# LM_HTR_001.net
KiCad netlist of a schematic drawn in Altium Designer
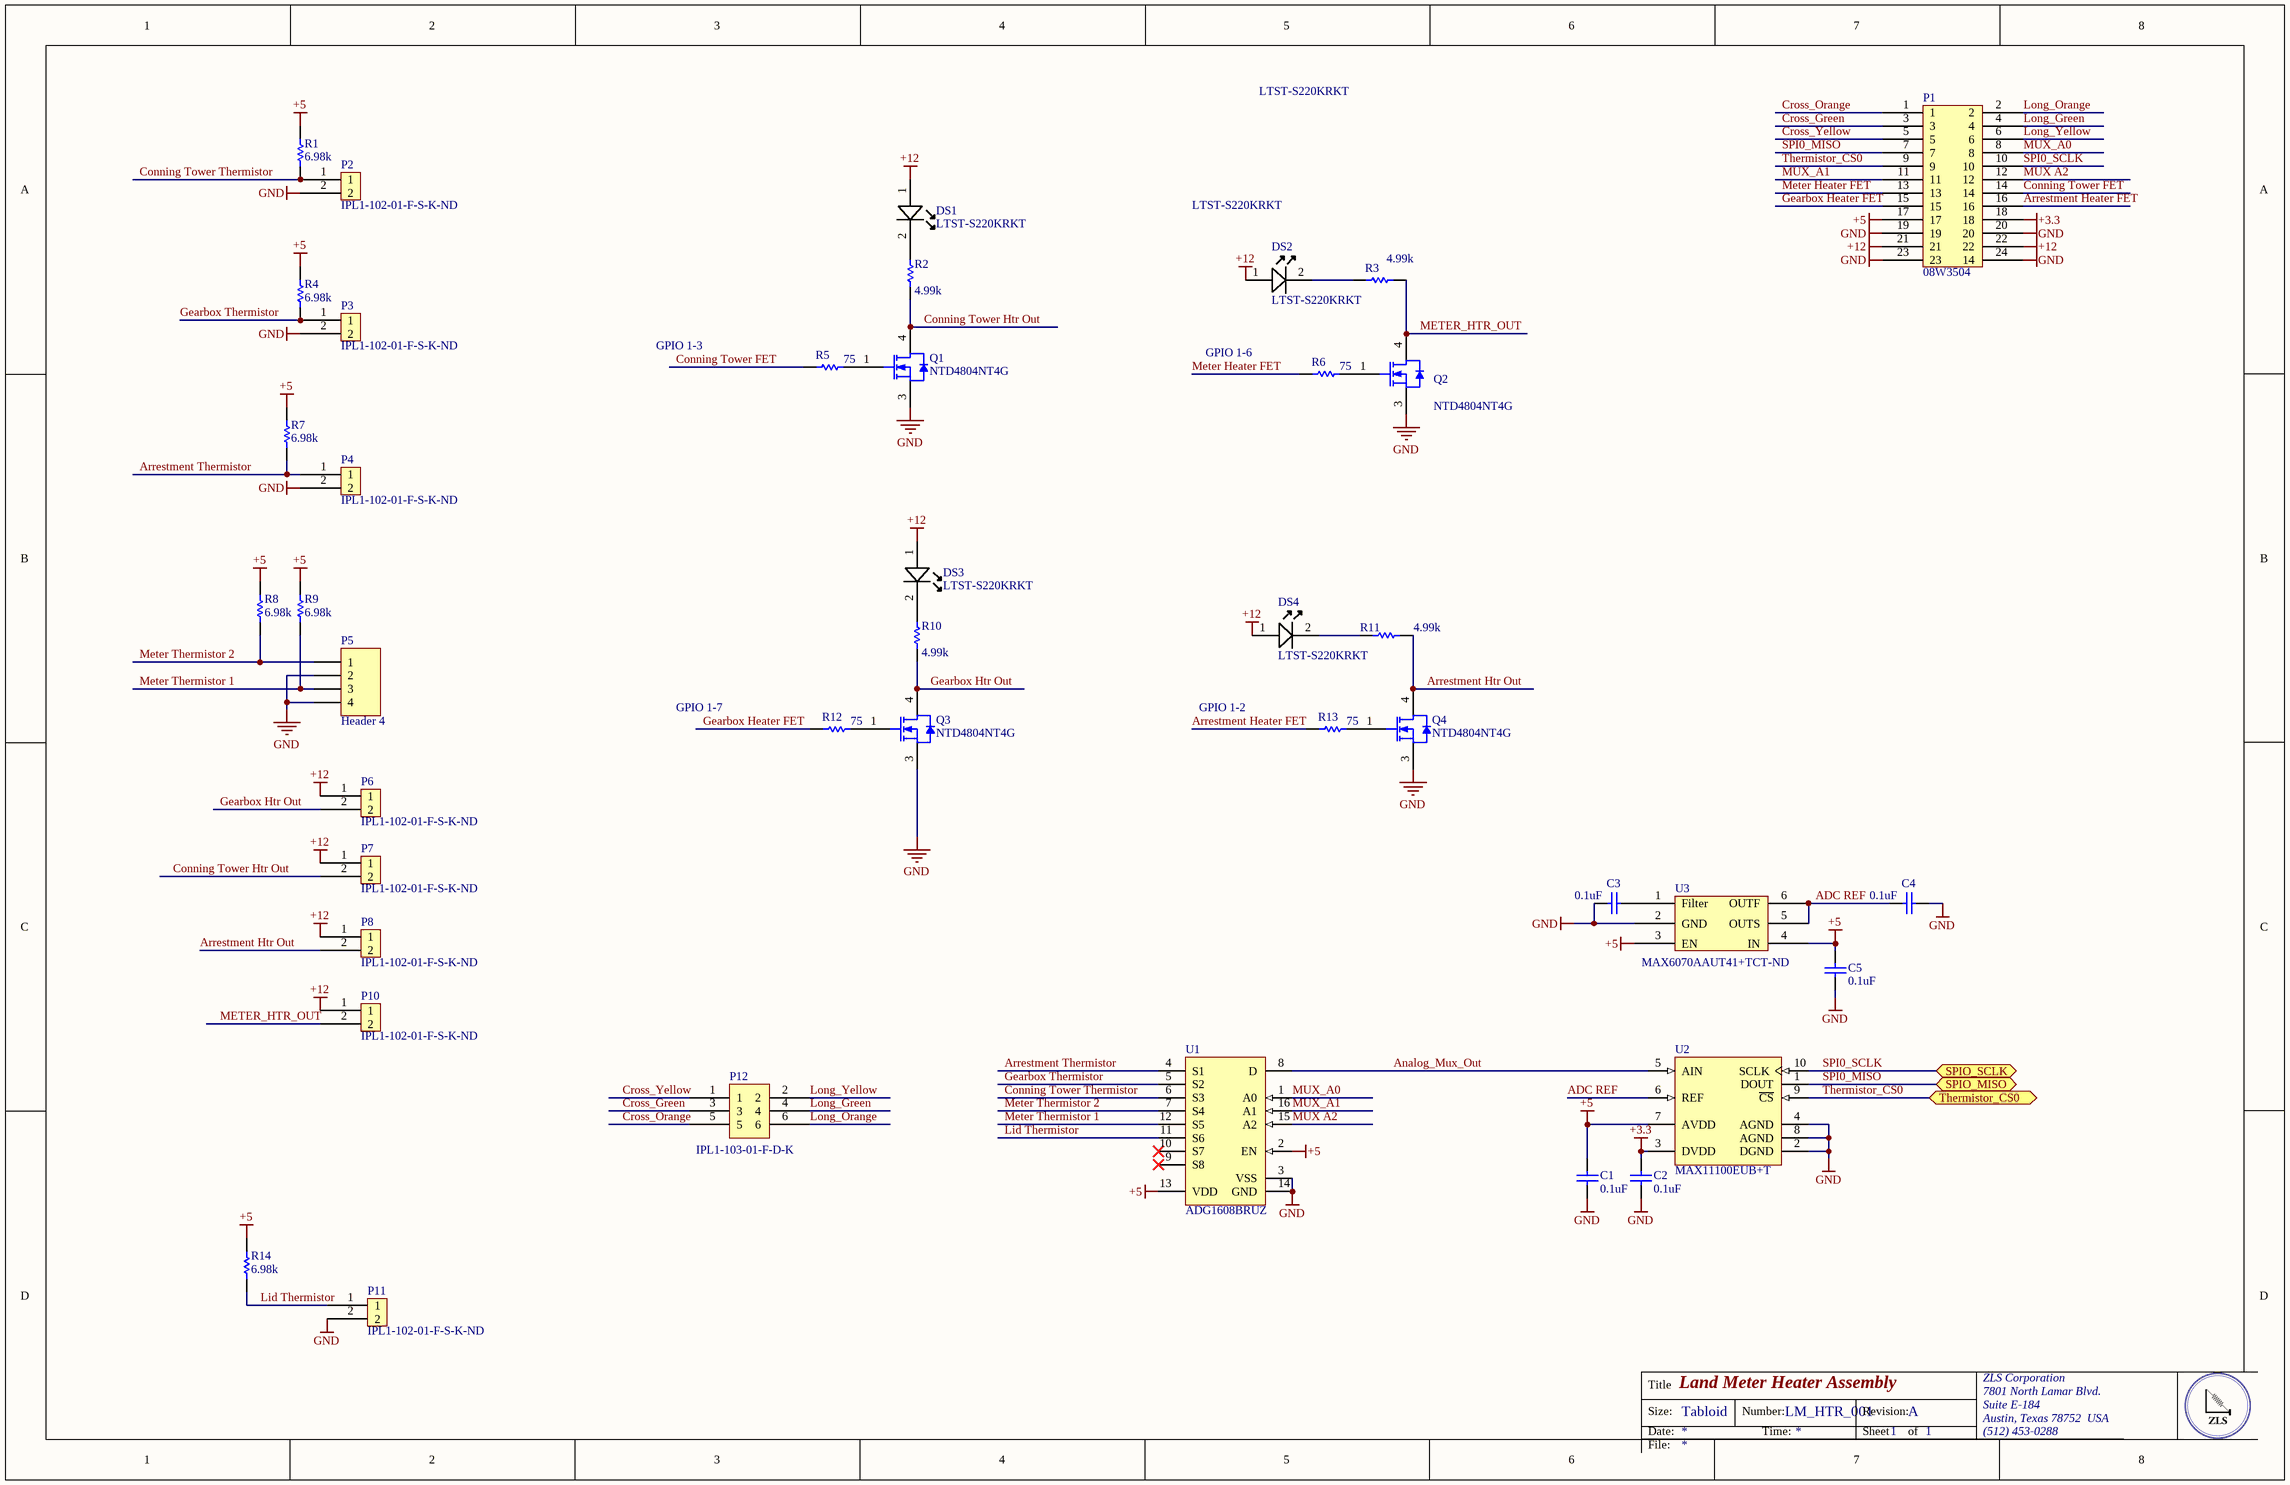
[diagram p0: LM_HTR_001.SchDoc]

(export (version "E")
  (design (tool "Eeschema 10.0.6"))
  (components
    (comp (ref "C1")
      (value "0.1uF")
      (footprint "CAPC0402(1005)60_L")
      (description "CAP CER 0.1UF 10V X7R 0402")
      (fields
        (field (name "MANUFACTURER") "Murata Electronics North America")
        (field (name "MANUFACTURER PART NUMBER") "GRM155R71A104KA01D")
      )
      (libsource (lib "Altium Content Vault") (part "CMP-1034-00252-1"))
    )
    (comp (ref "C2")
      (value "0.1uF")
      (footprint "CAPC0402(1005)60_L")
      (description "CAP CER 0.1UF 10V X7R 0402")
      (fields
        (field (name "MANUFACTURER") "Murata Electronics North America")
        (field (name "MANUFACTURER PART NUMBER") "GRM155R71A104KA01D")
      )
      (libsource (lib "Altium Content Vault") (part "CMP-1034-00252-1"))
    )
    (comp (ref "C3")
      (value "0.1uF")
      (footprint "CAPC0402(1005)60_L")
      (description "CAP CER 0.1UF 10V X7R 0402")
      (fields
        (field (name "MANUFACTURER") "Murata Electronics North America")
        (field (name "MANUFACTURER PART NUMBER") "GRM155R71A104KA01D")
      )
      (libsource (lib "Altium Content Vault") (part "CMP-1034-00252-1"))
    )
    (comp (ref "C4")
      (value "0.1uF")
      (footprint "CAPC0402(1005)60_L")
      (description "CAP CER 0.1UF 10V X7R 0402")
      (fields
        (field (name "MANUFACTURER") "Murata Electronics North America")
        (field (name "MANUFACTURER PART NUMBER") "GRM155R71A104KA01D")
      )
      (libsource (lib "Altium Content Vault") (part "CMP-1034-00252-1"))
    )
    (comp (ref "C5")
      (value "0.1uF")
      (footprint "CAPC0402(1005)60_L")
      (description "CAP CER 0.1UF 10V X7R 0402")
      (fields
        (field (name "MANUFACTURER") "Murata Electronics North America")
        (field (name "MANUFACTURER PART NUMBER") "GRM155R71A104KA01D")
      )
      (libsource (lib "Altium Content Vault") (part "CMP-1034-00252-1"))
    )
    (comp (ref "DS1")
      (value "Visible Name Value Type    False Description Lite-On LTST-S220KRKT Red LED, 631 nm 2012 (0805) Side View, Rectangle Lens SMD package STRING")
      (footprint "0805C_L")
      (fields
        (field (name "MANUFACTURER") "Vishay / Lite-On")
        (field (name "MANUFACTURER PART NUMBER") "LTST-S220KRKT")
      )
      (libsource (lib "*") (part "LED A/K"))
    )
    (comp (ref "DS2")
      (value "Visible Name Value Type    False Description Lite-On LTST-S220KRKT Red LED, 631 nm 2012 (0805) Side View, Rectangle Lens SMD package STRING")
      (footprint "0805C_L")
      (fields
        (field (name "MANUFACTURER") "Vishay / Lite-On")
        (field (name "MANUFACTURER PART NUMBER") "LTST-S220KRKT")
      )
      (libsource (lib "*") (part "LED A/K"))
    )
    (comp (ref "DS3")
      (value "Visible Name Value Type    False Description Lite-On LTST-S220KRKT Red LED, 631 nm 2012 (0805) Side View, Rectangle Lens SMD package STRING")
      (footprint "0805C_L")
      (fields
        (field (name "MANUFACTURER") "Vishay / Lite-On")
        (field (name "MANUFACTURER PART NUMBER") "LTST-S220KRKT")
      )
      (libsource (lib "*") (part "LED A/K"))
    )
    (comp (ref "DS4")
      (value "Visible Name Value Type    False Description Lite-On LTST-S220KRKT Red LED, 631 nm 2012 (0805) Side View, Rectangle Lens SMD package STRING")
      (footprint "0805C_L")
      (fields
        (field (name "MANUFACTURER") "Vishay / Lite-On")
        (field (name "MANUFACTURER PART NUMBER") "LTST-S220KRKT")
      )
      (libsource (lib "*") (part "LED A/K"))
    )
    (comp (ref "P1")
      (value "IPL1-112-01-F-S-K")
      (footprint "IPL1-112-01-F-S-K")
      (description "IPL1-112-01-F-D-K")
      (fields (field (name "SUPPLIER PART NUMBER 1") "08W3504"))
      (libsource (lib "ZLS_Schematic_lib") (part "IPL1-112-01-F-S-K"))
    )
    (comp (ref "P2")
      (value "IPL1-102-01-F-S-K")
      (footprint "IPL1-102-01-F-S-K")
      (description ".100 TERMINAL ASSEMBLY")
      (fields
        (field (name "SUPPLIER PART NUMBER 1") "IPL1-102-01-F-S-K-ND")
        (field (name "MANUFACTURER") "Samtec Inc.")
      )
      (libsource (lib "ZLS_Schematic_lib") (part "IPL1-102-01-F-S-K"))
    )
    (comp (ref "P3")
      (value "IPL1-102-01-F-S-K")
      (footprint "IPL1-102-01-F-S-K")
      (description ".100 TERMINAL ASSEMBLY")
      (fields
        (field (name "SUPPLIER PART NUMBER 1") "IPL1-102-01-F-S-K-ND")
        (field (name "MANUFACTURER") "Samtec Inc.")
      )
      (libsource (lib "ZLS_Schematic_lib") (part "IPL1-102-01-F-S-K"))
    )
    (comp (ref "P4")
      (value "IPL1-102-01-F-S-K")
      (footprint "IPL1-102-01-F-S-K")
      (description ".100 TERMINAL ASSEMBLY")
      (fields
        (field (name "SUPPLIER PART NUMBER 1") "IPL1-102-01-F-S-K-ND")
        (field (name "MANUFACTURER") "Samtec Inc.")
      )
      (libsource (lib "ZLS_Schematic_lib") (part "IPL1-102-01-F-S-K"))
    )
    (comp (ref "P5")
      (value "Header 4")
      (footprint "IPL1-104-01-L-S-K")
      (description "Header, 4-Pin")
      (fields (field (name "PUBLISHER") "Altium Limited"))
      (libsource (lib "Miscellaneous Connectors") (part "Header 4"))
    )
    (comp (ref "P6")
      (value "IPL1-102-01-F-S-K")
      (footprint "IPL1-102-01-F-S-K")
      (description ".100 TERMINAL ASSEMBLY")
      (fields
        (field (name "SUPPLIER PART NUMBER 1") "IPL1-102-01-F-S-K-ND")
        (field (name "MANUFACTURER") "Samtec Inc.")
      )
      (libsource (lib "ZLS_Schematic_lib") (part "IPL1-102-01-F-S-K"))
    )
    (comp (ref "P7")
      (value "IPL1-102-01-F-S-K")
      (footprint "IPL1-102-01-F-S-K")
      (description ".100 TERMINAL ASSEMBLY")
      (fields
        (field (name "SUPPLIER PART NUMBER 1") "IPL1-102-01-F-S-K-ND")
        (field (name "MANUFACTURER") "Samtec Inc.")
      )
      (libsource (lib "ZLS_Schematic_lib") (part "IPL1-102-01-F-S-K"))
    )
    (comp (ref "P8")
      (value "IPL1-102-01-F-S-K")
      (footprint "IPL1-102-01-F-S-K")
      (description ".100 TERMINAL ASSEMBLY")
      (fields
        (field (name "SUPPLIER PART NUMBER 1") "IPL1-102-01-F-S-K-ND")
        (field (name "MANUFACTURER") "Samtec Inc.")
      )
      (libsource (lib "ZLS_Schematic_lib") (part "IPL1-102-01-F-S-K"))
    )
    (comp (ref "P10")
      (value "IPL1-102-01-F-S-K")
      (footprint "IPL1-102-01-F-S-K")
      (description ".100 TERMINAL ASSEMBLY")
      (fields
        (field (name "SUPPLIER PART NUMBER 1") "IPL1-102-01-F-S-K-ND")
        (field (name "MANUFACTURER") "Samtec Inc.")
      )
      (libsource (lib "ZLS_Schematic_lib") (part "IPL1-102-01-F-S-K"))
    )
    (comp (ref "P11")
      (value "IPL1-102-01-F-S-K")
      (footprint "IPL1-102-01-F-S-K")
      (description ".100 TERMINAL ASSEMBLY")
      (fields
        (field (name "SUPPLIER PART NUMBER 1") "IPL1-102-01-F-S-K-ND")
        (field (name "MANUFACTURER") "Samtec Inc.")
      )
      (libsource (lib "ZLS_Schematic_lib") (part "IPL1-102-01-F-S-K"))
    )
    (comp (ref "P12")
      (value "IPL1-103-01-F-D")
      (footprint "IPL1-103-01-F-D")
      (fields
        (field (name "MANUFACTURER") "SAMTEC")
        (field (name "MANUFACTURER PART NUMBER") "IPL1-103-01-F-D-K")
        (field (name "COMPONENTLINK1URL") "https://webassistants.partcommunity.com/23d-libs/samtec/search/resolve.html?EMAIL=mysamtec@samtec.com&PN=HTSW-114-05-F-D")
        (field (name "COMPONENTLINK1DESCRIPTION") "https://webassistants.partcommunity.com/23d-libs/samtec/search/resolve.html?EMAIL=mysamtec@samtec.com&PN=HTSW-114-05-F-D")
      )
      (libsource (lib "ZLS_Schematic_lib") (part "IPL1-103-01-F-D"))
    )
    (comp (ref "Q1")
      (value "NTD4804NT4G")
      (footprint "ONSC-DPAK-3-369AA-01_V")
      (description "Power MOSFET, 30 V, 117 A, Single N-Channel, 3-Pin DPAK, Pb-Free, Tape and Reel")
      (fields (field (name "MANUFACTURER") "On Semiconductor"))
      (libsource (lib "Altium Content Vault") (part "CMP-1058-00341-1"))
    )
    (comp (ref "Q2")
      (value "NTD4804NT4G")
      (footprint "ONSC-DPAK-3-369AA-01_V")
      (description "Power MOSFET, 30 V, 117 A, Single N-Channel, 3-Pin DPAK, Pb-Free, Tape and Reel")
      (fields (field (name "MANUFACTURER") "On Semiconductor"))
      (libsource (lib "Altium Content Vault") (part "CMP-1058-00341-1"))
    )
    (comp (ref "Q3")
      (value "NTD4804NT4G")
      (footprint "ONSC-DPAK-3-369AA-01_V")
      (description "Power MOSFET, 30 V, 117 A, Single N-Channel, 3-Pin DPAK, Pb-Free, Tape and Reel")
      (fields (field (name "MANUFACTURER") "On Semiconductor"))
      (libsource (lib "Altium Content Vault") (part "CMP-1058-00341-1"))
    )
    (comp (ref "Q4")
      (value "NTD4804NT4G")
      (footprint "ONSC-DPAK-3-369AA-01_V")
      (description "Power MOSFET, 30 V, 117 A, Single N-Channel, 3-Pin DPAK, Pb-Free, Tape and Reel")
      (fields (field (name "MANUFACTURER") "On Semiconductor"))
      (libsource (lib "Altium Content Vault") (part "CMP-1058-00341-1"))
    )
    (comp (ref "R1")
      (value "6K98 1% 0805(2012)")
      (footprint "RESC0805(2012)_N")
      (description "6K98 0.125W 1% 0805 (2012 Metric)  SMD")
      (fields
        (field (name "MANUFACTURER") "Vishay Dale")
        (field (name "MANUFACTURER PART NUMBER") "CRCW08056K98FKEA")
        (field (name "RESISTANCE (OHMS)") "6.98k")
      )
      (libsource (lib "Altium Content Vault") (part "CMP-1013-00606-1"))
    )
    (comp (ref "R2")
      (value "~")
      (footprint "RESC0805(2012)_L")
      (fields
        (field (name "MANUFACTURER") "Vishay Dale")
        (field (name "MANUFACTURER PART NUMBER") "CRCW08054K99FKEA")
        (field (name "RESISTANCE (OHMS)") "4.99k")
        (field (name "TOLERANCE") "±1%")
      )
      (libsource (lib "Altium Content Vault") (part "CMP-1013-00393-1"))
    )
    (comp (ref "R3")
      (value "~")
      (footprint "RESC0805(2012)_L")
      (fields
        (field (name "MANUFACTURER") "Vishay Dale")
        (field (name "MANUFACTURER PART NUMBER") "CRCW08054K99FKEA")
        (field (name "RESISTANCE (OHMS)") "4.99k")
        (field (name "TOLERANCE") "±1%")
      )
      (libsource (lib "Altium Content Vault") (part "CMP-1013-00393-1"))
    )
    (comp (ref "R4")
      (value "6K98 1% 0805(2012)")
      (footprint "RESC0805(2012)_N")
      (description "6K98 0.125W 1% 0805 (2012 Metric)  SMD")
      (fields
        (field (name "MANUFACTURER") "Vishay Dale")
        (field (name "MANUFACTURER PART NUMBER") "CRCW08056K98FKEA")
        (field (name "RESISTANCE (OHMS)") "6.98k")
      )
      (libsource (lib "Altium Content Vault") (part "CMP-1013-00606-1"))
    )
    (comp (ref "R5")
      (value "~")
      (footprint "RESC0805(2012)_L")
      (fields
        (field (name "MANUFACTURER") "Vishay Dale")
        (field (name "MANUFACTURER PART NUMBER") "CRCW080575R0FKEA")
        (field (name "RESISTANCE (OHMS)") "75")
        (field (name "TOLERANCE") "±1%")
      )
      (libsource (lib "Altium Content Vault") (part "CMP-1013-00393-1"))
    )
    (comp (ref "R6")
      (value "~")
      (footprint "RESC0805(2012)_L")
      (fields
        (field (name "MANUFACTURER") "Vishay Dale")
        (field (name "MANUFACTURER PART NUMBER") "CRCW080575R0FKEA")
        (field (name "RESISTANCE (OHMS)") "75")
        (field (name "TOLERANCE") "±1%")
      )
      (libsource (lib "Altium Content Vault") (part "CMP-1013-00393-1"))
    )
    (comp (ref "R7")
      (value "6K98 1% 0805(2012)")
      (footprint "RESC0805(2012)_N")
      (description "6K98 0.125W 1% 0805 (2012 Metric)  SMD")
      (fields
        (field (name "MANUFACTURER") "Vishay Dale")
        (field (name "MANUFACTURER PART NUMBER") "CRCW08056K98FKEA")
        (field (name "RESISTANCE (OHMS)") "6.98k")
      )
      (libsource (lib "Altium Content Vault") (part "CMP-1013-00606-1"))
    )
    (comp (ref "R8")
      (value "6K98 1% 0805(2012)")
      (footprint "RESC0805(2012)_N")
      (description "6K98 0.125W 1% 0805 (2012 Metric)  SMD")
      (fields
        (field (name "MANUFACTURER") "Vishay Dale")
        (field (name "MANUFACTURER PART NUMBER") "CRCW08056K98FKEA")
        (field (name "RESISTANCE (OHMS)") "6.98k")
      )
      (libsource (lib "Altium Content Vault") (part "CMP-1013-00606-1"))
    )
    (comp (ref "R9")
      (value "6K98 1% 0805(2012)")
      (footprint "RESC0805(2012)_N")
      (description "6K98 0.125W 1% 0805 (2012 Metric)  SMD")
      (fields
        (field (name "MANUFACTURER") "Vishay Dale")
        (field (name "MANUFACTURER PART NUMBER") "CRCW08056K98FKEA")
        (field (name "RESISTANCE (OHMS)") "6.98k")
      )
      (libsource (lib "Altium Content Vault") (part "CMP-1013-00606-1"))
    )
    (comp (ref "R10")
      (value "~")
      (footprint "RESC0805(2012)_L")
      (fields
        (field (name "MANUFACTURER") "Vishay Dale")
        (field (name "MANUFACTURER PART NUMBER") "CRCW08054K99FKEA")
        (field (name "RESISTANCE (OHMS)") "4.99k")
        (field (name "TOLERANCE") "±1%")
      )
      (libsource (lib "Altium Content Vault") (part "CMP-1013-00393-1"))
    )
    (comp (ref "R11")
      (value "~")
      (footprint "RESC0805(2012)_L")
      (fields
        (field (name "MANUFACTURER") "Vishay Dale")
        (field (name "MANUFACTURER PART NUMBER") "CRCW08054K99FKEA")
        (field (name "RESISTANCE (OHMS)") "4.99k")
        (field (name "TOLERANCE") "±1%")
      )
      (libsource (lib "Altium Content Vault") (part "CMP-1013-00393-1"))
    )
    (comp (ref "R12")
      (value "~")
      (footprint "RESC0805(2012)_L")
      (fields
        (field (name "MANUFACTURER") "Vishay Dale")
        (field (name "MANUFACTURER PART NUMBER") "CRCW080575R0FKEA")
        (field (name "RESISTANCE (OHMS)") "75")
        (field (name "TOLERANCE") "±1%")
      )
      (libsource (lib "Altium Content Vault") (part "CMP-1013-00393-1"))
    )
    (comp (ref "R13")
      (value "~")
      (footprint "RESC0805(2012)_L")
      (fields
        (field (name "MANUFACTURER") "Vishay Dale")
        (field (name "MANUFACTURER PART NUMBER") "CRCW080575R0FKEA")
        (field (name "RESISTANCE (OHMS)") "75")
        (field (name "TOLERANCE") "±1%")
      )
      (libsource (lib "Altium Content Vault") (part "CMP-1013-00393-1"))
    )
    (comp (ref "R14")
      (value "6K98 1% 0805(2012)")
      (footprint "RESC0805(2012)_N")
      (description "6K98 0.125W 1% 0805 (2012 Metric)  SMD")
      (fields
        (field (name "MANUFACTURER") "Vishay Dale")
        (field (name "MANUFACTURER PART NUMBER") "CRCW08056K98FKEA")
        (field (name "RESISTANCE (OHMS)") "6.98k")
      )
      (libsource (lib "Altium Content Vault") (part "CMP-1013-00606-1"))
    )
    (comp (ref "U1")
      (value "ADG1608BRUZ")
      (footprint "ADI-RU-16_M")
      (description "4.5 Ohm Ron, 8-Channel +/-5 V,+12 V, +5 V and +3.3 V Multiplexer, 16-pin SOP (RU-16), Tube")
      (fields (field (name "MANUFACTURER") "Analog Devices"))
      (libsource (lib "Altium Content Vault") (part "ADI-ADG1608-RU-16"))
    )
    (comp (ref "U2")
      (value "MAX11100EUB+T")
      (footprint "U10+2_L")
      (description "16-Bit, +5V, 200ksps ADC with 10uA Shutdown, 10-Pin uMAX, -40°C to +85°C, Pb-Free, Tape and Reel")
      (libsource (lib "Altium Content Vault") (part "CON-ADC-MAX11100-IL10"))
    )
    (comp (ref "U3")
      (value "MAX6070AAUT41+T")
      (footprint "SOT95P280X445-6N")
      (description "IC VREF SERIES 4.096V SOT23")
      (fields
        (field (name "SUPPLIER PART NUMBER 1") "MAX6070AAUT41+TCT-ND")
        (field (name "MANUFACTURER") "Maxim Integrated")
        (field (name "TOLERANCE") "±0.04%")
      )
      (libsource (lib "ZLS_Schematic_lib") (part "MAX6070AAUT41+T"))
    )
  )
  (nets
    (net (code "1") (name "+3.3") (class "Default")
      (node (ref "C2") (pin "1") (pinfunction "1_1") (pintype "passive"))
      (node (ref "P1") (pin "18") (pinfunction "18_18") (pintype "passive"))
      (node (ref "U2") (pin "3") (pinfunction "DVDD_3") (pintype "power_in"))
    )
    (net (code "2") (name "+5") (class "Default")
      (node (ref "C1") (pin "1") (pinfunction "1_1") (pintype "passive"))
      (node (ref "C5") (pin "1") (pinfunction "1_1") (pintype "passive"))
      (node (ref "P1") (pin "17") (pinfunction "17_17") (pintype "passive"))
      (node (ref "R1") (pin "2") (pinfunction "2_2") (pintype "passive"))
      (node (ref "R14") (pin "1") (pinfunction "1_1") (pintype "passive"))
      (node (ref "R4") (pin "2") (pinfunction "2_2") (pintype "passive"))
      (node (ref "R7") (pin "1") (pinfunction "1_1") (pintype "passive"))
      (node (ref "R8") (pin "1") (pinfunction "1_1") (pintype "passive"))
      (node (ref "R9") (pin "2") (pinfunction "2_2") (pintype "passive"))
      (node (ref "U1") (pin "13") (pinfunction "VDD_13") (pintype "power_in"))
      (node (ref "U1") (pin "2") (pinfunction "EN_2") (pintype "input"))
      (node (ref "U2") (pin "7") (pinfunction "AVDD_7") (pintype "power_in"))
      (node (ref "U3") (pin "3") (pinfunction "EN_3") (pintype "passive"))
      (node (ref "U3") (pin "4") (pinfunction "IN_4") (pintype "passive"))
    )
    (net (code "3") (name "+12") (class "Default")
      (node (ref "DS1") (pin "1") (pinfunction "A_1") (pintype "passive"))
      (node (ref "DS2") (pin "1") (pinfunction "A_1") (pintype "passive"))
      (node (ref "DS3") (pin "1") (pinfunction "A_1") (pintype "passive"))
      (node (ref "DS4") (pin "1") (pinfunction "A_1") (pintype "passive"))
      (node (ref "P1") (pin "21") (pinfunction "21_21") (pintype "passive"))
      (node (ref "P1") (pin "22") (pinfunction "22_22") (pintype "passive"))
      (node (ref "P10") (pin "1") (pinfunction "1_1") (pintype "passive"))
      (node (ref "P6") (pin "1") (pinfunction "1_1") (pintype "passive"))
      (node (ref "P7") (pin "1") (pinfunction "1_1") (pintype "passive"))
      (node (ref "P8") (pin "1") (pinfunction "1_1") (pintype "passive"))
    )
    (net (code "4") (name "/ADC REF") (class "Default")
      (node (ref "C4") (pin "2") (pinfunction "2_2") (pintype "passive"))
      (node (ref "U2") (pin "6") (pinfunction "REF_6") (pintype "input"))
      (node (ref "U3") (pin "5") (pinfunction "OUTS_5") (pintype "passive"))
      (node (ref "U3") (pin "6") (pinfunction "OUTF_6") (pintype "passive"))
    )
    (net (code "5") (name "/Analog_Mux_Out") (class "Default")
      (node (ref "U1") (pin "8") (pinfunction "D_8") (pintype "passive"))
      (node (ref "U2") (pin "5") (pinfunction "AIN_5") (pintype "input"))
    )
    (net (code "6") (name "/Arrestment Heater FET") (class "Default")
      (node (ref "P1") (pin "16") (pinfunction "16_16") (pintype "passive"))
      (node (ref "R13") (pin "1") (pinfunction "1_1") (pintype "passive"))
    )
    (net (code "7") (name "/Arrestment Htr Out") (class "Default")
      (node (ref "P8") (pin "2") (pinfunction "2_2") (pintype "passive"))
      (node (ref "Q4") (pin "4") (pinfunction "D_4") (pintype "passive"))
      (node (ref "R11") (pin "2") (pinfunction "2_2") (pintype "passive"))
    )
    (net (code "8") (name "/Arrestment Thermistor") (class "Default")
      (node (ref "P4") (pin "1") (pinfunction "1_1") (pintype "passive"))
      (node (ref "R7") (pin "2") (pinfunction "2_2") (pintype "passive"))
      (node (ref "U1") (pin "4") (pinfunction "S1_4") (pintype "passive"))
    )
    (net (code "9") (name "/Conning Tower FET") (class "Default")
      (node (ref "P1") (pin "14") (pinfunction "14_14") (pintype "passive"))
      (node (ref "R5") (pin "1") (pinfunction "1_1") (pintype "passive"))
    )
    (net (code "10") (name "/Conning Tower Htr Out") (class "Default")
      (node (ref "P7") (pin "2") (pinfunction "2_2") (pintype "passive"))
      (node (ref "Q1") (pin "4") (pinfunction "D_4") (pintype "passive"))
      (node (ref "R2") (pin "1") (pinfunction "1_1") (pintype "passive"))
    )
    (net (code "11") (name "/Conning Tower Thermistor") (class "Default")
      (node (ref "P2") (pin "1") (pinfunction "1_1") (pintype "passive"))
      (node (ref "R1") (pin "1") (pinfunction "1_1") (pintype "passive"))
      (node (ref "U1") (pin "6") (pinfunction "S3_6") (pintype "passive"))
    )
    (net (code "12") (name "/Cross_Green") (class "Default")
      (node (ref "P1") (pin "3") (pinfunction "3_3") (pintype "passive"))
      (node (ref "P12") (pin "3") (pinfunction "3_3") (pintype "passive"))
    )
    (net (code "13") (name "/Cross_Orange") (class "Default")
      (node (ref "P1") (pin "1") (pinfunction "1_1") (pintype "passive"))
      (node (ref "P12") (pin "5") (pinfunction "5_5") (pintype "passive"))
    )
    (net (code "14") (name "/Cross_Yellow") (class "Default")
      (node (ref "P1") (pin "5") (pinfunction "5_5") (pintype "passive"))
      (node (ref "P12") (pin "1") (pinfunction "1_1") (pintype "passive"))
    )
    (net (code "15") (name "/Gearbox Heater FET") (class "Default")
      (node (ref "P1") (pin "15") (pinfunction "15_15") (pintype "passive"))
      (node (ref "R12") (pin "1") (pinfunction "1_1") (pintype "passive"))
    )
    (net (code "16") (name "/Gearbox Htr Out") (class "Default")
      (node (ref "P6") (pin "2") (pinfunction "2_2") (pintype "passive"))
      (node (ref "Q3") (pin "4") (pinfunction "D_4") (pintype "passive"))
      (node (ref "R10") (pin "1") (pinfunction "1_1") (pintype "passive"))
    )
    (net (code "17") (name "/Gearbox Thermistor") (class "Default")
      (node (ref "P3") (pin "1") (pinfunction "1_1") (pintype "passive"))
      (node (ref "R4") (pin "1") (pinfunction "1_1") (pintype "passive"))
      (node (ref "U1") (pin "5") (pinfunction "S2_5") (pintype "passive"))
    )
    (net (code "18") (name "/Lid Thermistor") (class "Default")
      (node (ref "P11") (pin "1") (pinfunction "1_1") (pintype "passive"))
      (node (ref "R14") (pin "2") (pinfunction "2_2") (pintype "passive"))
      (node (ref "U1") (pin "11") (pinfunction "S6_11") (pintype "passive"))
    )
    (net (code "19") (name "/Long_Green") (class "Default")
      (node (ref "P1") (pin "4") (pinfunction "4_4") (pintype "passive"))
      (node (ref "P12") (pin "4") (pinfunction "4_4") (pintype "passive"))
    )
    (net (code "20") (name "/Long_Orange") (class "Default")
      (node (ref "P1") (pin "2") (pinfunction "2_2") (pintype "passive"))
      (node (ref "P12") (pin "6") (pinfunction "6_6") (pintype "passive"))
    )
    (net (code "21") (name "/Long_Yellow") (class "Default")
      (node (ref "P1") (pin "6") (pinfunction "6_6") (pintype "passive"))
      (node (ref "P12") (pin "2") (pinfunction "2_2") (pintype "passive"))
    )
    (net (code "22") (name "/METER_HTR_OUT") (class "Default")
      (node (ref "P10") (pin "2") (pinfunction "2_2") (pintype "passive"))
      (node (ref "Q2") (pin "4") (pinfunction "D_4") (pintype "passive"))
      (node (ref "R3") (pin "2") (pinfunction "2_2") (pintype "passive"))
    )
    (net (code "23") (name "/MUX A2") (class "Default")
      (node (ref "P1") (pin "12") (pinfunction "12_12") (pintype "passive"))
      (node (ref "U1") (pin "15") (pinfunction "A2_15") (pintype "input"))
    )
    (net (code "24") (name "/MUX_A0") (class "Default")
      (node (ref "P1") (pin "8") (pinfunction "8_8") (pintype "passive"))
      (node (ref "U1") (pin "1") (pinfunction "A0_1") (pintype "input"))
    )
    (net (code "25") (name "/MUX_A1") (class "Default")
      (node (ref "P1") (pin "11") (pinfunction "11_11") (pintype "passive"))
      (node (ref "U1") (pin "16") (pinfunction "A1_16") (pintype "input"))
    )
    (net (code "26") (name "/Meter Heater FET") (class "Default")
      (node (ref "P1") (pin "13") (pinfunction "13_13") (pintype "passive"))
      (node (ref "R6") (pin "1") (pinfunction "1_1") (pintype "passive"))
    )
    (net (code "27") (name "/Meter Thermistor 1") (class "Default")
      (node (ref "P5") (pin "3") (pinfunction "3_3") (pintype "passive"))
      (node (ref "R9") (pin "1") (pinfunction "1_1") (pintype "passive"))
      (node (ref "U1") (pin "12") (pinfunction "S5_12") (pintype "passive"))
    )
    (net (code "28") (name "/Meter Thermistor 2") (class "Default")
      (node (ref "P5") (pin "1") (pinfunction "1_1") (pintype "passive"))
      (node (ref "R8") (pin "2") (pinfunction "2_2") (pintype "passive"))
      (node (ref "U1") (pin "7") (pinfunction "S4_7") (pintype "passive"))
    )
    (net (code "29") (name "/SPI0_MISO") (class "Default")
      (node (ref "P1") (pin "7") (pinfunction "7_7") (pintype "passive"))
      (node (ref "U2") (pin "1") (pinfunction "DOUT_1") (pintype "tri_state"))
    )
    (net (code "30") (name "/SPI0_SCLK") (class "Default")
      (node (ref "P1") (pin "10") (pinfunction "10_10") (pintype "passive"))
      (node (ref "U2") (pin "10") (pinfunction "SCLK_10") (pintype "input"))
    )
    (net (code "31") (name "/Thermistor_CS0") (class "Default")
      (node (ref "P1") (pin "9") (pinfunction "9_9") (pintype "passive"))
      (node (ref "U2") (pin "9") (pinfunction "~{CS}_9") (pintype "input"))
    )
    (net (code "32") (name "GND") (class "Default")
      (node (ref "C1") (pin "2") (pinfunction "2_2") (pintype "passive"))
      (node (ref "C2") (pin "2") (pinfunction "2_2") (pintype "passive"))
      (node (ref "C3") (pin "2") (pinfunction "2_2") (pintype "passive"))
      (node (ref "C4") (pin "1") (pinfunction "1_1") (pintype "passive"))
      (node (ref "C5") (pin "2") (pinfunction "2_2") (pintype "passive"))
      (node (ref "P1") (pin "19") (pinfunction "19_19") (pintype "passive"))
      (node (ref "P1") (pin "20") (pinfunction "20_20") (pintype "passive"))
      (node (ref "P1") (pin "23") (pinfunction "23_23") (pintype "passive"))
      (node (ref "P1") (pin "24") (pinfunction "14_24") (pintype "passive"))
      (node (ref "P11") (pin "2") (pinfunction "2_2") (pintype "passive"))
      (node (ref "P2") (pin "2") (pinfunction "2_2") (pintype "passive"))
      (node (ref "P3") (pin "2") (pinfunction "2_2") (pintype "passive"))
      (node (ref "P4") (pin "2") (pinfunction "2_2") (pintype "passive"))
      (node (ref "P5") (pin "2") (pinfunction "2_2") (pintype "passive"))
      (node (ref "P5") (pin "4") (pinfunction "4_4") (pintype "passive"))
      (node (ref "Q1") (pin "3") (pinfunction "S_3") (pintype "passive"))
      (node (ref "Q2") (pin "3") (pinfunction "S_3") (pintype "passive"))
      (node (ref "Q3") (pin "3") (pinfunction "S_3") (pintype "passive"))
      (node (ref "Q4") (pin "3") (pinfunction "S_3") (pintype "passive"))
      (node (ref "U1") (pin "14") (pinfunction "GND_14") (pintype "power_in"))
      (node (ref "U1") (pin "3") (pinfunction "VSS_3") (pintype "power_in"))
      (node (ref "U2") (pin "2") (pinfunction "DGND_2") (pintype "power_in"))
      (node (ref "U2") (pin "4") (pinfunction "AGND_4") (pintype "power_in"))
      (node (ref "U2") (pin "8") (pinfunction "AGND_8") (pintype "power_in"))
      (node (ref "U3") (pin "2") (pinfunction "GND_2") (pintype "passive"))
    )
    (net (code "33") (name "Net-(DS1-K)") (class "Default")
      (node (ref "DS1") (pin "2") (pinfunction "K_2") (pintype "passive"))
      (node (ref "R2") (pin "2") (pinfunction "2_2") (pintype "passive"))
    )
    (net (code "34") (name "Net-(DS2-K)") (class "Default")
      (node (ref "DS2") (pin "2") (pinfunction "K_2") (pintype "passive"))
      (node (ref "R3") (pin "1") (pinfunction "1_1") (pintype "passive"))
    )
    (net (code "35") (name "Net-(DS3-K)") (class "Default")
      (node (ref "DS3") (pin "2") (pinfunction "K_2") (pintype "passive"))
      (node (ref "R10") (pin "2") (pinfunction "2_2") (pintype "passive"))
    )
    (net (code "36") (name "Net-(DS4-K)") (class "Default")
      (node (ref "DS4") (pin "2") (pinfunction "K_2") (pintype "passive"))
      (node (ref "R11") (pin "1") (pinfunction "1_1") (pintype "passive"))
    )
    (net (code "37") (name "Net-(Q1-G)") (class "Default")
      (node (ref "Q1") (pin "1") (pinfunction "G_1") (pintype "passive"))
      (node (ref "R5") (pin "2") (pinfunction "2_2") (pintype "passive"))
    )
    (net (code "38") (name "Net-(Q2-G)") (class "Default")
      (node (ref "Q2") (pin "1") (pinfunction "G_1") (pintype "passive"))
      (node (ref "R6") (pin "2") (pinfunction "2_2") (pintype "passive"))
    )
    (net (code "39") (name "Net-(Q3-G)") (class "Default")
      (node (ref "Q3") (pin "1") (pinfunction "G_1") (pintype "passive"))
      (node (ref "R12") (pin "2") (pinfunction "2_2") (pintype "passive"))
    )
    (net (code "40") (name "Net-(Q4-G)") (class "Default")
      (node (ref "Q4") (pin "1") (pinfunction "G_1") (pintype "passive"))
      (node (ref "R13") (pin "2") (pinfunction "2_2") (pintype "passive"))
    )
    (net (code "41") (name "Net-(U3-Filter)") (class "Default")
      (node (ref "C3") (pin "1") (pinfunction "1_1") (pintype "passive"))
      (node (ref "U3") (pin "1") (pinfunction "Filter_1") (pintype "passive"))
    )
    (net (code "42") (name "unconnected-(U1-S7-Pad10)") (class "Default")
      (node (ref "U1") (pin "10") (pinfunction "S7_10") (pintype "passive+no_connect"))
    )
    (net (code "43") (name "unconnected-(U1-S8-Pad9)") (class "Default")
      (node (ref "U1") (pin "9") (pinfunction "S8_9") (pintype "passive+no_connect"))
    )
  )
)
